# table6.net
KiCad netlist of a schematic drawn in EasyEDA
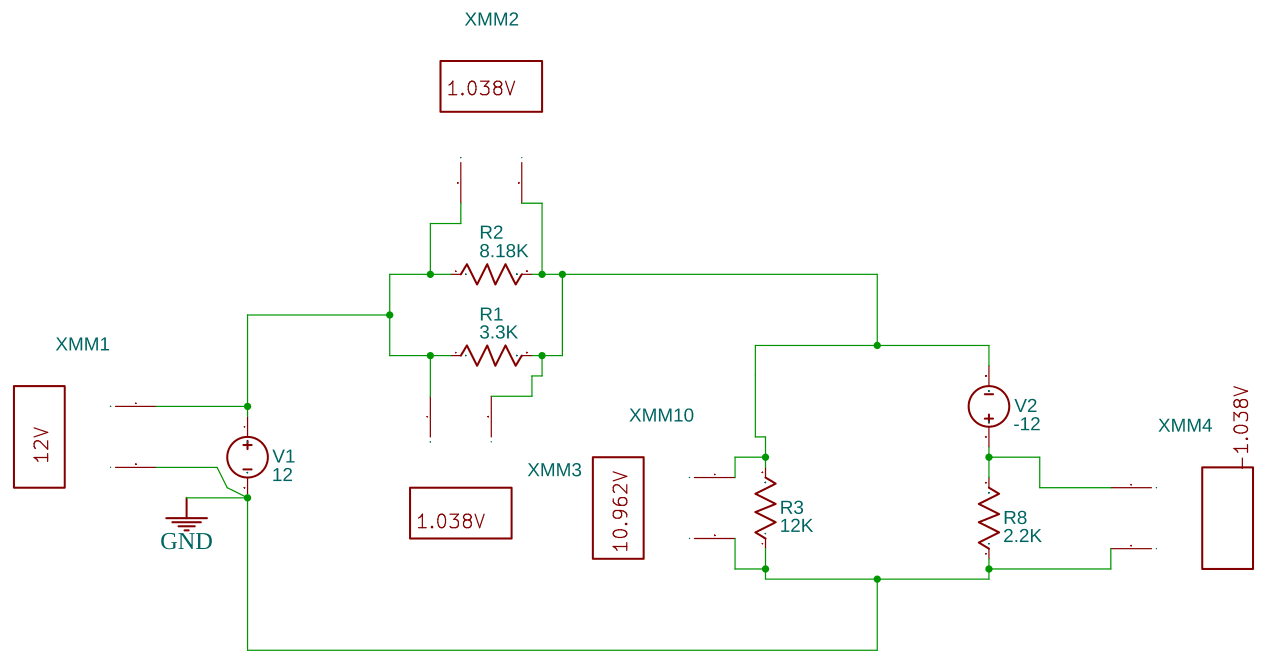
[diagram p0: schematic sheet]

(export (version "E")
  (design (tool "Eeschema 10.0.6"))
  (components
    (comp (ref "R1") (value "3.3K") (libsource (lib "") (part "Resistor_US_1")))
    (comp (ref "R2") (value "8.18K") (libsource (lib "") (part "Resistor_US_1")))
    (comp (ref "R3") (value "12K") (libsource (lib "") (part "Resistor_US")))
    (comp (ref "R8") (value "2.2K") (libsource (lib "") (part "Resistor_US")))
    (comp (ref "V1") (value "12") (libsource (lib "") (part "VDC_1")))
    (comp (ref "V2") (value "-12") (libsource (lib "") (part "VDC")))
    (comp (ref "XMM1") (value "Multimeter") (libsource (lib "") (part "MULTIMETER_4")))
    (comp (ref "XMM2") (value "Multimeter") (libsource (lib "") (part "MULTIMETER_3")))
    (comp (ref "XMM3") (value "Multimeter") (libsource (lib "") (part "MULTIMETER_2")))
    (comp (ref "XMM4") (value "Multimeter") (libsource (lib "") (part "MULTIMETER")))
    (comp (ref "XMM10") (value "Multimeter") (libsource (lib "") (part "MULTIMETER_1")))
  )
  (nets
    (net (code "1") (name "GND") (class "Default")
      (node (ref "R3") (pin "1") (pinfunction "1_1") (pintype "unspecified"))
      (node (ref "R8") (pin "1") (pinfunction "1_1") (pintype "unspecified"))
      (node (ref "V1") (pin "2") (pinfunction "2_2") (pintype "unspecified"))
      (node (ref "XMM1") (pin "2") (pinfunction "I_2") (pintype "unspecified"))
      (node (ref "XMM10") (pin "2") (pinfunction "I_2") (pintype "unspecified"))
      (node (ref "XMM4") (pin "2") (pinfunction "I_2") (pintype "unspecified"))
    )
    (net (code "2") (name "Net-(XMM1-+)") (class "Default")
      (node (ref "R1") (pin "1") (pinfunction "1_1") (pintype "unspecified"))
      (node (ref "R2") (pin "1") (pinfunction "1_1") (pintype "unspecified"))
      (node (ref "V1") (pin "1") (pinfunction "1_1") (pintype "unspecified"))
      (node (ref "XMM1") (pin "1") (pinfunction "+_1") (pintype "unspecified"))
      (node (ref "XMM2") (pin "1") (pinfunction "+_1") (pintype "unspecified"))
      (node (ref "XMM3") (pin "1") (pinfunction "+_1") (pintype "unspecified"))
    )
    (net (code "3") (name "Net-(XMM4-+)") (class "Default")
      (node (ref "R8") (pin "2") (pinfunction "2_2") (pintype "unspecified"))
      (node (ref "V2") (pin "1") (pinfunction "1_1") (pintype "unspecified"))
      (node (ref "XMM4") (pin "1") (pinfunction "+_1") (pintype "unspecified"))
    )
    (net (code "4") (name "Net-(XMM10-+)") (class "Default")
      (node (ref "R1") (pin "2") (pinfunction "2_2") (pintype "unspecified"))
      (node (ref "R2") (pin "2") (pinfunction "2_2") (pintype "unspecified"))
      (node (ref "R3") (pin "2") (pinfunction "2_2") (pintype "unspecified"))
      (node (ref "V2") (pin "2") (pinfunction "2_2") (pintype "unspecified"))
      (node (ref "XMM10") (pin "1") (pinfunction "+_1") (pintype "unspecified"))
      (node (ref "XMM2") (pin "2") (pinfunction "I_2") (pintype "unspecified"))
      (node (ref "XMM3") (pin "2") (pinfunction "I_2") (pintype "unspecified"))
    )
  )
)
